# PLL1.net
KiCad netlist of a schematic drawn in Altium Designer
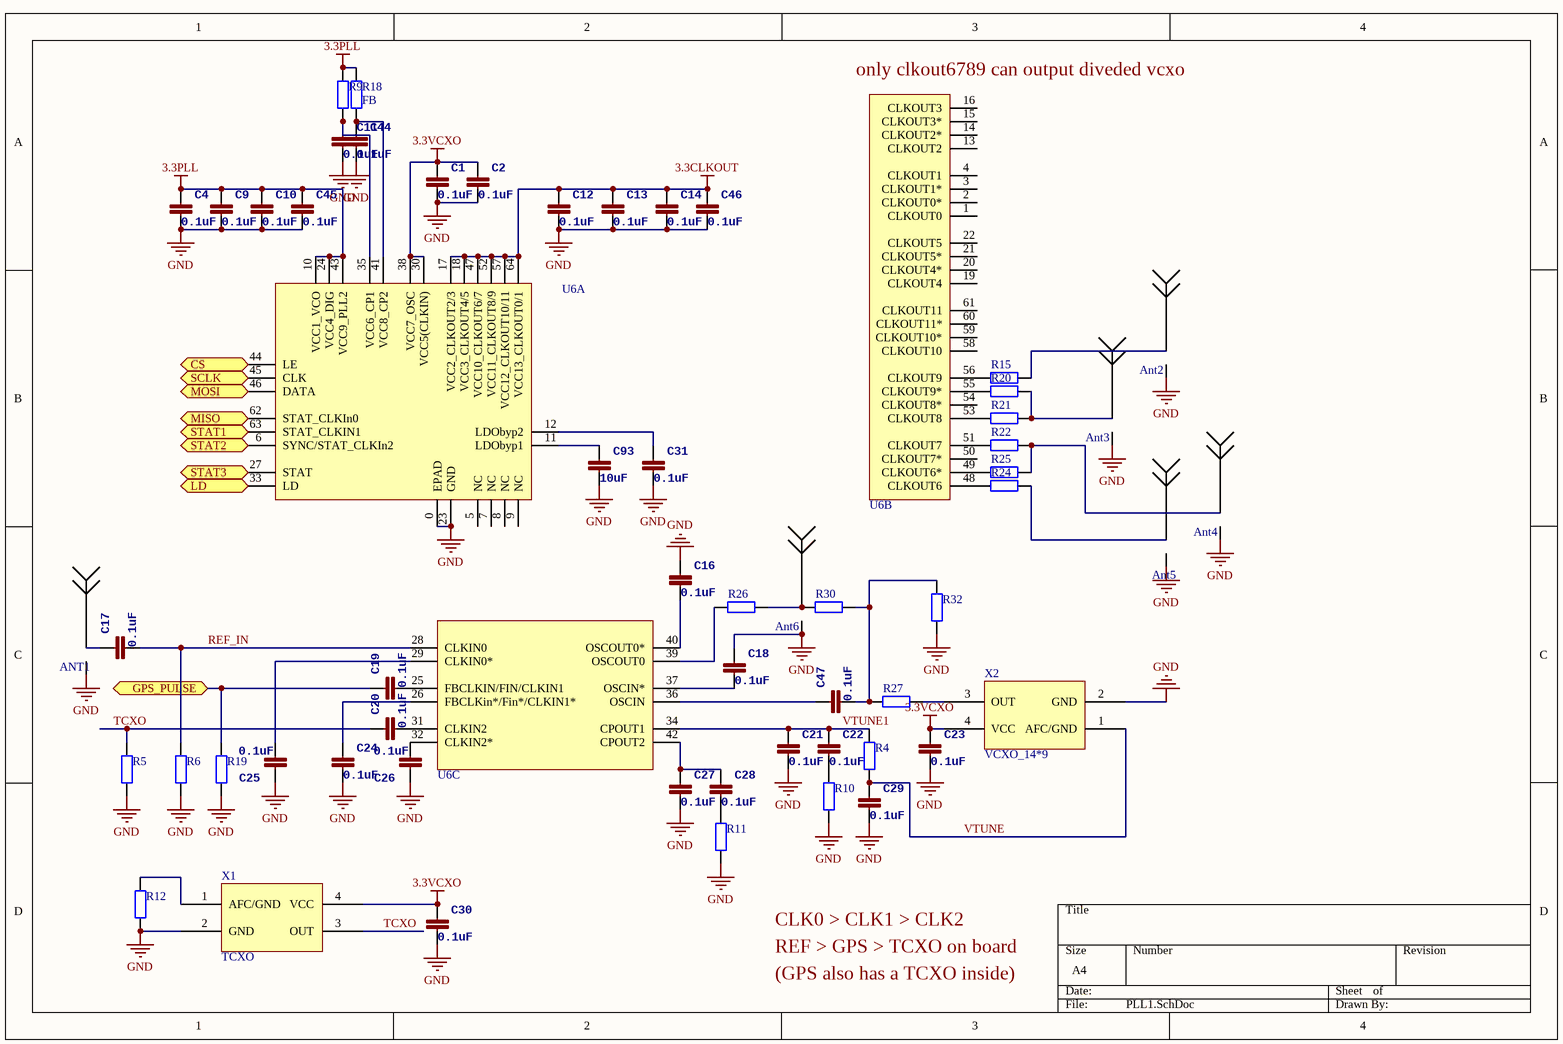
[diagram p0: PLL1.SchDoc]

(export (version "E")
  (design (tool "Eeschema 10.0.6"))
  (components
    (comp (ref "ANT1") (value "Antenna") (footprint "SMA-2B") (libsource (lib "F4SDR") (part "Antenna")))
    (comp (ref "Ant2") (value "Antenna") (footprint "SMA-2B") (libsource (lib "F4SDR") (part "Antenna")))
    (comp (ref "Ant3") (value "Antenna") (footprint "SMA-2B") (libsource (lib "F4SDR") (part "Antenna")))
    (comp (ref "Ant4") (value "Antenna") (footprint "SMA-2B") (libsource (lib "F4SDR") (part "Antenna")))
    (comp (ref "Ant5") (value "Antenna") (footprint "SMA-2B") (libsource (lib "F4SDR") (part "Antenna")))
    (comp (ref "Ant6") (value "Antenna") (footprint "SMA-2B") (libsource (lib "F4SDR") (part "Antenna")))
    (comp (ref "C1")
      (value "0.1uF")
      (footprint "0402")
      (description "<b>Capacitor</b>\nStandard 0603 ceramic capacitor, and 0.1\" leaded capacitor.")
      (fields (field (name "PARTNO") "CC0402ZRY5V7BB104"))
      (libsource (lib "pixhawk2") (part "CAP0402-CAP"))
    )
    (comp (ref "C2")
      (value "0.1uF")
      (footprint "0402")
      (description "<b>Capacitor</b>\nStandard 0603 ceramic capacitor, and 0.1\" leaded capacitor.")
      (fields (field (name "PARTNO") "CC0402ZRY5V7BB104"))
      (libsource (lib "pixhawk2") (part "CAP0402-CAP"))
    )
    (comp (ref "C4")
      (value "0.1uF")
      (footprint "0402")
      (description "<b>Capacitor</b>\nStandard 0603 ceramic capacitor, and 0.1\" leaded capacitor.")
      (fields (field (name "PARTNO") "CC0402ZRY5V7BB104"))
      (libsource (lib "pixhawk2") (part "CAP0402-CAP"))
    )
    (comp (ref "C9")
      (value "0.1uF")
      (footprint "0402")
      (description "<b>Capacitor</b>\nStandard 0603 ceramic capacitor, and 0.1\" leaded capacitor.")
      (fields (field (name "PARTNO") "CC0402ZRY5V7BB104"))
      (libsource (lib "pixhawk2") (part "CAP0402-CAP"))
    )
    (comp (ref "C10")
      (value "0.1uF")
      (footprint "0402")
      (description "<b>Capacitor</b>\nStandard 0603 ceramic capacitor, and 0.1\" leaded capacitor.")
      (fields (field (name "PARTNO") "CC0402ZRY5V7BB104"))
      (libsource (lib "pixhawk2") (part "CAP0402-CAP"))
    )
    (comp (ref "C11")
      (value "0.1uF")
      (footprint "0402")
      (description "<b>Capacitor</b>\nStandard 0603 ceramic capacitor, and 0.1\" leaded capacitor.")
      (fields (field (name "PARTNO") "CC0402ZRY5V7BB104"))
      (libsource (lib "pixhawk2") (part "CAP0402-CAP"))
    )
    (comp (ref "C12")
      (value "0.1uF")
      (footprint "0402")
      (description "<b>Capacitor</b>\nStandard 0603 ceramic capacitor, and 0.1\" leaded capacitor.")
      (fields (field (name "PARTNO") "CC0402ZRY5V7BB104"))
      (libsource (lib "pixhawk2") (part "CAP0402-CAP"))
    )
    (comp (ref "C13")
      (value "0.1uF")
      (footprint "0402")
      (description "<b>Capacitor</b>\nStandard 0603 ceramic capacitor, and 0.1\" leaded capacitor.")
      (fields (field (name "PARTNO") "CC0402ZRY5V7BB104"))
      (libsource (lib "pixhawk2") (part "CAP0402-CAP"))
    )
    (comp (ref "C14")
      (value "0.1uF")
      (footprint "0402")
      (description "<b>Capacitor</b>\nStandard 0603 ceramic capacitor, and 0.1\" leaded capacitor.")
      (fields (field (name "PARTNO") "CC0402ZRY5V7BB104"))
      (libsource (lib "pixhawk2") (part "CAP0402-CAP"))
    )
    (comp (ref "C16")
      (value "0.1uF")
      (footprint "0402")
      (description "<b>Capacitor</b>\nStandard 0603 ceramic capacitor, and 0.1\" leaded capacitor.")
      (fields (field (name "PARTNO") "CC0402ZRY5V7BB104"))
      (libsource (lib "pixhawk2") (part "CAP0402-CAP"))
    )
    (comp (ref "C17")
      (value "0.1uF")
      (footprint "0402")
      (description "<b>Capacitor</b>\nStandard 0603 ceramic capacitor, and 0.1\" leaded capacitor.")
      (fields (field (name "PARTNO") "CC0402ZRY5V7BB104"))
      (libsource (lib "") (part "CAP0402-CAP_1"))
    )
    (comp (ref "C18")
      (value "0.1uF")
      (footprint "0402")
      (description "<b>Capacitor</b>\nStandard 0603 ceramic capacitor, and 0.1\" leaded capacitor.")
      (fields (field (name "PARTNO") "CC0402ZRY5V7BB104"))
      (libsource (lib "pixhawk2") (part "CAP0402-CAP"))
    )
    (comp (ref "C19")
      (value "0.1uF")
      (footprint "0402")
      (description "<b>Capacitor</b>\nStandard 0603 ceramic capacitor, and 0.1\" leaded capacitor.")
      (fields (field (name "PARTNO") "CC0402ZRY5V7BB104"))
      (libsource (lib "") (part "CAP0402-CAP_1"))
    )
    (comp (ref "C20")
      (value "0.1uF")
      (footprint "0402")
      (description "<b>Capacitor</b>\nStandard 0603 ceramic capacitor, and 0.1\" leaded capacitor.")
      (fields (field (name "PARTNO") "CC0402ZRY5V7BB104"))
      (libsource (lib "") (part "CAP0402-CAP_1"))
    )
    (comp (ref "C21")
      (value "0.1uF")
      (footprint "0402")
      (description "<b>Capacitor</b>\nStandard 0603 ceramic capacitor, and 0.1\" leaded capacitor.")
      (fields (field (name "PARTNO") "CC0402ZRY5V7BB104"))
      (libsource (lib "pixhawk2") (part "CAP0402-CAP"))
    )
    (comp (ref "C22")
      (value "0.1uF")
      (footprint "0402")
      (description "<b>Capacitor</b>\nStandard 0603 ceramic capacitor, and 0.1\" leaded capacitor.")
      (fields (field (name "PARTNO") "CC0402ZRY5V7BB104"))
      (libsource (lib "pixhawk2") (part "CAP0402-CAP"))
    )
    (comp (ref "C23")
      (value "0.1uF")
      (footprint "0402")
      (description "<b>Capacitor</b>\nStandard 0603 ceramic capacitor, and 0.1\" leaded capacitor.")
      (fields (field (name "PARTNO") "CC0402ZRY5V7BB104"))
      (libsource (lib "pixhawk2") (part "CAP0402-CAP"))
    )
    (comp (ref "C24")
      (value "0.1uF")
      (footprint "0402")
      (description "<b>Capacitor</b>\nStandard 0603 ceramic capacitor, and 0.1\" leaded capacitor.")
      (fields (field (name "PARTNO") "CC0402ZRY5V7BB104"))
      (libsource (lib "pixhawk2") (part "CAP0402-CAP"))
    )
    (comp (ref "C25")
      (value "0.1uF")
      (footprint "0402")
      (description "<b>Capacitor</b>\nStandard 0603 ceramic capacitor, and 0.1\" leaded capacitor.")
      (fields (field (name "PARTNO") "CC0402ZRY5V7BB104"))
      (libsource (lib "") (part "CAP0402-CAP_2"))
    )
    (comp (ref "C26")
      (value "0.1uF")
      (footprint "0402")
      (description "<b>Capacitor</b>\nStandard 0603 ceramic capacitor, and 0.1\" leaded capacitor.")
      (fields (field (name "PARTNO") "CC0402ZRY5V7BB104"))
      (libsource (lib "") (part "CAP0402-CAP_2"))
    )
    (comp (ref "C27")
      (value "0.1uF")
      (footprint "0402")
      (description "<b>Capacitor</b>\nStandard 0603 ceramic capacitor, and 0.1\" leaded capacitor.")
      (fields (field (name "PARTNO") "CC0402ZRY5V7BB104"))
      (libsource (lib "pixhawk2") (part "CAP0402-CAP"))
    )
    (comp (ref "C28")
      (value "0.1uF")
      (footprint "0402")
      (description "<b>Capacitor</b>\nStandard 0603 ceramic capacitor, and 0.1\" leaded capacitor.")
      (fields (field (name "PARTNO") "CC0402ZRY5V7BB104"))
      (libsource (lib "pixhawk2") (part "CAP0402-CAP"))
    )
    (comp (ref "C29")
      (value "0.1uF")
      (footprint "0402")
      (description "<b>Capacitor</b>\nStandard 0603 ceramic capacitor, and 0.1\" leaded capacitor.")
      (fields (field (name "PARTNO") "CC0402ZRY5V7BB104"))
      (libsource (lib "pixhawk2") (part "CAP0402-CAP"))
    )
    (comp (ref "C30")
      (value "0.1uF")
      (footprint "0402")
      (description "<b>Capacitor</b>\nStandard 0603 ceramic capacitor, and 0.1\" leaded capacitor.")
      (fields (field (name "PARTNO") "CC0402ZRY5V7BB104"))
      (libsource (lib "pixhawk2") (part "CAP0402-CAP"))
    )
    (comp (ref "C31")
      (value "0.1uF")
      (footprint "0402")
      (description "<b>Capacitor</b>\nStandard 0603 ceramic capacitor, and 0.1\" leaded capacitor.")
      (fields (field (name "PARTNO") "CC0402ZRY5V7BB104"))
      (libsource (lib "pixhawk2") (part "CAP0402-CAP"))
    )
    (comp (ref "C44")
      (value "0.1uF")
      (footprint "0402")
      (description "<b>Capacitor</b>\nStandard 0603 ceramic capacitor, and 0.1\" leaded capacitor.")
      (fields (field (name "PARTNO") "CC0402ZRY5V7BB104"))
      (libsource (lib "pixhawk2") (part "CAP0402-CAP"))
    )
    (comp (ref "C45")
      (value "0.1uF")
      (footprint "0402")
      (description "<b>Capacitor</b>\nStandard 0603 ceramic capacitor, and 0.1\" leaded capacitor.")
      (fields (field (name "PARTNO") "CC0402ZRY5V7BB104"))
      (libsource (lib "pixhawk2") (part "CAP0402-CAP"))
    )
    (comp (ref "C46")
      (value "0.1uF")
      (footprint "0402")
      (description "<b>Capacitor</b>\nStandard 0603 ceramic capacitor, and 0.1\" leaded capacitor.")
      (fields (field (name "PARTNO") "CC0402ZRY5V7BB104"))
      (libsource (lib "pixhawk2") (part "CAP0402-CAP"))
    )
    (comp (ref "C47")
      (value "0.1uF")
      (footprint "0402")
      (description "<b>Capacitor</b>\nStandard 0603 ceramic capacitor, and 0.1\" leaded capacitor.")
      (fields (field (name "PARTNO") "CC0402ZRY5V7BB104"))
      (libsource (lib "") (part "CAP0402-CAP_1"))
    )
    (comp (ref "C93")
      (value "10uF")
      (footprint "0603L")
      (description "<b>Capacitor</b>\nStandard 0603 ceramic capacitor, and 0.1\" leaded capacitor.")
      (fields (field (name "PARTNO") "CC0402ZRY5V7BB104"))
      (libsource (lib "pixhawk2") (part "CAP0402-CAP"))
    )
    (comp (ref "R4")
      (value "~")
      (footprint "0402")
      (description "Resistor")
      (fields (field (name "PUBLISHER") "Altium Limited"))
      (libsource (lib "") (part "Res2_1"))
    )
    (comp (ref "R5")
      (value "~")
      (footprint "0402")
      (description "Resistor")
      (fields (field (name "PUBLISHER") "Altium Limited"))
      (libsource (lib "Miscellaneous Devices") (part "Res2"))
    )
    (comp (ref "R6")
      (value "~")
      (footprint "0402")
      (description "Resistor")
      (fields (field (name "PUBLISHER") "Altium Limited"))
      (libsource (lib "") (part "Res2_1"))
    )
    (comp (ref "R9")
      (value "~")
      (footprint "0402")
      (description "Resistor")
      (fields (field (name "PUBLISHER") "Altium Limited"))
      (libsource (lib "Miscellaneous Devices") (part "Res2"))
    )
    (comp (ref "R10")
      (value "~")
      (footprint "0402")
      (description "Resistor")
      (fields (field (name "PUBLISHER") "Altium Limited"))
      (libsource (lib "") (part "Res2_1"))
    )
    (comp (ref "R11")
      (value "~")
      (footprint "0402")
      (description "Resistor")
      (fields (field (name "PUBLISHER") "Altium Limited"))
      (libsource (lib "") (part "Res2_1"))
    )
    (comp (ref "R12")
      (value "~")
      (footprint "0402")
      (description "Resistor")
      (fields (field (name "PUBLISHER") "Altium Limited"))
      (libsource (lib "") (part "Res2_1"))
    )
    (comp (ref "R15")
      (value "~")
      (footprint "0402")
      (description "Resistor")
      (fields (field (name "PUBLISHER") "Altium Limited"))
      (libsource (lib "") (part "Res2_2"))
    )
    (comp (ref "R18")
      (value "FB")
      (footprint "0402")
      (description "Resistor")
      (fields (field (name "PUBLISHER") "Altium Limited"))
      (libsource (lib "Miscellaneous Devices") (part "Res2"))
    )
    (comp (ref "R19")
      (value "~")
      (footprint "0402")
      (description "Resistor")
      (fields (field (name "PUBLISHER") "Altium Limited"))
      (libsource (lib "Miscellaneous Devices") (part "Res2"))
    )
    (comp (ref "R20")
      (value "~")
      (footprint "0402")
      (description "Resistor")
      (fields (field (name "PUBLISHER") "Altium Limited"))
      (libsource (lib "") (part "Res2_2"))
    )
    (comp (ref "R21")
      (value "~")
      (footprint "0402")
      (description "Resistor")
      (fields (field (name "PUBLISHER") "Altium Limited"))
      (libsource (lib "") (part "Res2_2"))
    )
    (comp (ref "R22")
      (value "~")
      (footprint "0402")
      (description "Resistor")
      (fields (field (name "PUBLISHER") "Altium Limited"))
      (libsource (lib "") (part "Res2_2"))
    )
    (comp (ref "R24")
      (value "~")
      (footprint "0402")
      (description "Resistor")
      (fields (field (name "PUBLISHER") "Altium Limited"))
      (libsource (lib "") (part "Res2_2"))
    )
    (comp (ref "R25")
      (value "~")
      (footprint "0402")
      (description "Resistor")
      (fields (field (name "PUBLISHER") "Altium Limited"))
      (libsource (lib "") (part "Res2_2"))
    )
    (comp (ref "R26")
      (value "~")
      (footprint "0402")
      (description "Resistor")
      (fields (field (name "PUBLISHER") "Altium Limited"))
      (libsource (lib "") (part "Res2_2"))
    )
    (comp (ref "R27")
      (value "~")
      (footprint "0402")
      (description "Resistor")
      (fields (field (name "PUBLISHER") "Altium Limited"))
      (libsource (lib "") (part "Res2_2"))
    )
    (comp (ref "R30")
      (value "~")
      (footprint "0402")
      (description "Resistor")
      (fields (field (name "PUBLISHER") "Altium Limited"))
      (libsource (lib "") (part "Res2_2"))
    )
    (comp (ref "R32")
      (value "~")
      (footprint "0402")
      (description "Resistor")
      (fields (field (name "PUBLISHER") "Altium Limited"))
      (libsource (lib "") (part "Res2_1"))
    )
    (comp (ref "U6") (value "LMK04816") (footprint "LMK04816") (libsource (lib "F4SDR") (part "LMK04816")))
    (comp (ref "X1") (value "TCXO") (footprint "TXC_7Q") (libsource (lib "F4SDR") (part "OSC_40M")))
    (comp (ref "X2") (value "VCXO_14*9") (footprint "CRYSTEK-9*14") (libsource (lib "") (part "OSC_40M_1")))
  )
  (nets
    (net (code "1") (name "/CS") (class "Default")
      (node (ref "U6") (pin "44") (pinfunction "LE_44") (pintype "passive"))
    )
    (net (code "2") (name "/GPS_PULSE") (class "Default")
      (node (ref "C19") (pin "1") (pinfunction "1_1") (pintype "passive"))
      (node (ref "R19") (pin "2") (pinfunction "2_2") (pintype "passive"))
    )
    (net (code "3") (name "/LD") (class "Default")
      (node (ref "U6") (pin "33") (pinfunction "LD_33") (pintype "passive"))
    )
    (net (code "4") (name "/MISO") (class "Default")
      (node (ref "U6") (pin "62") (pinfunction "STAT_CLKIn0_62") (pintype "passive"))
    )
    (net (code "5") (name "/MOSI") (class "Default")
      (node (ref "U6") (pin "46") (pinfunction "DATA_46") (pintype "passive"))
    )
    (net (code "6") (name "/REF_IN") (class "Default")
      (node (ref "C17") (pin "2") (pinfunction "2_2") (pintype "passive"))
      (node (ref "R6") (pin "1") (pinfunction "1_1") (pintype "passive"))
      (node (ref "U6") (pin "28") (pinfunction "CLKIN0_28") (pintype "passive"))
    )
    (net (code "7") (name "/SCLK") (class "Default")
      (node (ref "U6") (pin "45") (pinfunction "CLK_45") (pintype "passive"))
    )
    (net (code "8") (name "/STAT1") (class "Default")
      (node (ref "U6") (pin "63") (pinfunction "STAT_CLKIN1_63") (pintype "passive"))
    )
    (net (code "9") (name "/STAT2") (class "Default")
      (node (ref "U6") (pin "6") (pinfunction "SYNC/STAT_CLKIn2_6") (pintype "passive"))
    )
    (net (code "10") (name "/STAT3") (class "Default")
      (node (ref "U6") (pin "27") (pinfunction "STAT_27") (pintype "passive"))
    )
    (net (code "11") (name "/TCXO") (class "Default")
      (node (ref "C20") (pin "1") (pinfunction "1_1") (pintype "passive"))
      (node (ref "R5") (pin "2") (pinfunction "2_2") (pintype "passive"))
      (node (ref "X1") (pin "3") (pinfunction "OUT_3") (pintype "passive"))
    )
    (net (code "12") (name "/VTUNE") (class "Default")
      (node (ref "C29") (pin "1") (pinfunction "1_1") (pintype "passive"))
      (node (ref "R4") (pin "2") (pinfunction "2_2") (pintype "passive"))
      (node (ref "X2") (pin "1") (pinfunction "AFC/GND_1") (pintype "passive"))
    )
    (net (code "13") (name "/VTUNE1") (class "Default")
      (node (ref "C21") (pin "1") (pinfunction "1_1") (pintype "passive"))
      (node (ref "C22") (pin "1") (pinfunction "1_1") (pintype "passive"))
      (node (ref "R4") (pin "1") (pinfunction "1_1") (pintype "passive"))
      (node (ref "U6") (pin "34") (pinfunction "CPOUT1_34") (pintype "passive"))
    )
    (net (code "14") (name "3.3CLKOUT") (class "Default")
      (node (ref "C12") (pin "1") (pinfunction "1_1") (pintype "passive"))
      (node (ref "C13") (pin "1") (pinfunction "1_1") (pintype "passive"))
      (node (ref "C14") (pin "1") (pinfunction "1_1") (pintype "passive"))
      (node (ref "C46") (pin "1") (pinfunction "1_1") (pintype "passive"))
      (node (ref "U6") (pin "17") (pinfunction "VCC2_CLKOUT2/3_17") (pintype "passive"))
      (node (ref "U6") (pin "18") (pinfunction "VCC3_CLKOUT4/5_18") (pintype "passive"))
      (node (ref "U6") (pin "47") (pinfunction "VCC10_CLKOUT6/7_47") (pintype "passive"))
      (node (ref "U6") (pin "52") (pinfunction "VCC11_CLKOUT8/9_52") (pintype "passive"))
      (node (ref "U6") (pin "57") (pinfunction "VCC12_CLKOUT10/11_57") (pintype "passive"))
      (node (ref "U6") (pin "64") (pinfunction "VCC13_CLKOUT0/1_64") (pintype "passive"))
    )
    (net (code "15") (name "3.3PLL") (class "Default")
      (node (ref "C10") (pin "1") (pinfunction "1_1") (pintype "passive"))
      (node (ref "C4") (pin "1") (pinfunction "1_1") (pintype "passive"))
      (node (ref "C45") (pin "1") (pinfunction "1_1") (pintype "passive"))
      (node (ref "C9") (pin "1") (pinfunction "1_1") (pintype "passive"))
      (node (ref "R18") (pin "2") (pinfunction "2_2") (pintype "passive"))
      (node (ref "R9") (pin "2") (pinfunction "2_2") (pintype "passive"))
      (node (ref "U6") (pin "10") (pinfunction "VCC1_VCO_10") (pintype "passive"))
      (node (ref "U6") (pin "24") (pinfunction "VCC4_DIG_24") (pintype "passive"))
      (node (ref "U6") (pin "43") (pinfunction "VCC9_PLL2_43") (pintype "passive"))
    )
    (net (code "16") (name "3.3VCXO") (class "Default")
      (node (ref "C1") (pin "1") (pinfunction "1_1") (pintype "passive"))
      (node (ref "C2") (pin "1") (pinfunction "1_1") (pintype "passive"))
      (node (ref "C23") (pin "1") (pinfunction "1_1") (pintype "passive"))
      (node (ref "C30") (pin "1") (pinfunction "1_1") (pintype "passive"))
      (node (ref "U6") (pin "30") (pinfunction "VCC5(CLKIN)_30") (pintype "passive"))
      (node (ref "U6") (pin "38") (pinfunction "VCC7_OSC_38") (pintype "passive"))
      (node (ref "X1") (pin "4") (pinfunction "VCC_4") (pintype "passive"))
      (node (ref "X2") (pin "4") (pinfunction "VCC_4") (pintype "passive"))
    )
    (net (code "17") (name "GND") (class "Default")
      (node (ref "ANT1") (pin "GND") (pinfunction "G_GND") (pintype "passive"))
      (node (ref "Ant2") (pin "GND") (pinfunction "G_GND") (pintype "passive"))
      (node (ref "Ant3") (pin "GND") (pinfunction "G_GND") (pintype "passive"))
      (node (ref "Ant4") (pin "GND") (pinfunction "G_GND") (pintype "passive"))
      (node (ref "Ant5") (pin "GND") (pinfunction "G_GND") (pintype "passive"))
      (node (ref "Ant6") (pin "GND") (pinfunction "G_GND") (pintype "passive"))
      (node (ref "C1") (pin "2") (pinfunction "2_2") (pintype "passive"))
      (node (ref "C10") (pin "2") (pinfunction "2_2") (pintype "passive"))
      (node (ref "C11") (pin "2") (pinfunction "2_2") (pintype "passive"))
      (node (ref "C12") (pin "2") (pinfunction "2_2") (pintype "passive"))
      (node (ref "C13") (pin "2") (pinfunction "2_2") (pintype "passive"))
      (node (ref "C14") (pin "2") (pinfunction "2_2") (pintype "passive"))
      (node (ref "C16") (pin "1") (pinfunction "1_1") (pintype "passive"))
      (node (ref "C18") (pin "1") (pinfunction "1_1") (pintype "passive"))
      (node (ref "C2") (pin "2") (pinfunction "2_2") (pintype "passive"))
      (node (ref "C21") (pin "2") (pinfunction "2_2") (pintype "passive"))
      (node (ref "C23") (pin "2") (pinfunction "2_2") (pintype "passive"))
      (node (ref "C24") (pin "2") (pinfunction "2_2") (pintype "passive"))
      (node (ref "C25") (pin "1") (pinfunction "1_1") (pintype "passive"))
      (node (ref "C26") (pin "1") (pinfunction "1_1") (pintype "passive"))
      (node (ref "C27") (pin "2") (pinfunction "2_2") (pintype "passive"))
      (node (ref "C29") (pin "2") (pinfunction "2_2") (pintype "passive"))
      (node (ref "C30") (pin "2") (pinfunction "2_2") (pintype "passive"))
      (node (ref "C31") (pin "2") (pinfunction "2_2") (pintype "passive"))
      (node (ref "C4") (pin "2") (pinfunction "2_2") (pintype "passive"))
      (node (ref "C44") (pin "2") (pinfunction "2_2") (pintype "passive"))
      (node (ref "C45") (pin "2") (pinfunction "2_2") (pintype "passive"))
      (node (ref "C46") (pin "2") (pinfunction "2_2") (pintype "passive"))
      (node (ref "C9") (pin "2") (pinfunction "2_2") (pintype "passive"))
      (node (ref "C93") (pin "2") (pinfunction "2_2") (pintype "passive"))
      (node (ref "R10") (pin "2") (pinfunction "2_2") (pintype "passive"))
      (node (ref "R11") (pin "2") (pinfunction "2_2") (pintype "passive"))
      (node (ref "R12") (pin "2") (pinfunction "2_2") (pintype "passive"))
      (node (ref "R19") (pin "1") (pinfunction "1_1") (pintype "passive"))
      (node (ref "R32") (pin "2") (pinfunction "2_2") (pintype "passive"))
      (node (ref "R5") (pin "1") (pinfunction "1_1") (pintype "passive"))
      (node (ref "R6") (pin "2") (pinfunction "2_2") (pintype "passive"))
      (node (ref "U6") (pin "0") (pinfunction "EPAD_0") (pintype "passive"))
      (node (ref "U6") (pin "23") (pinfunction "GND_23") (pintype "passive"))
      (node (ref "X1") (pin "2") (pinfunction "GND_2") (pintype "passive"))
      (node (ref "X2") (pin "2") (pinfunction "GND_2") (pintype "passive"))
    )
    (net (code "18") (name "Net-(ANT1-Pad1)") (class "Default")
      (node (ref "ANT1") (pin "1") (pinfunction "1_1") (pintype "passive"))
      (node (ref "C17") (pin "1") (pinfunction "1_1") (pintype "passive"))
    )
    (net (code "19") (name "Net-(Ant2-Pad1)") (class "Default")
      (node (ref "Ant2") (pin "1") (pinfunction "1_1") (pintype "passive"))
      (node (ref "R15") (pin "2") (pinfunction "2_2") (pintype "passive"))
    )
    (net (code "20") (name "Net-(Ant3-Pad1)") (class "Default")
      (node (ref "Ant3") (pin "1") (pinfunction "1_1") (pintype "passive"))
      (node (ref "R20") (pin "2") (pinfunction "2_2") (pintype "passive"))
      (node (ref "R21") (pin "2") (pinfunction "2_2") (pintype "passive"))
    )
    (net (code "21") (name "Net-(Ant4-Pad1)") (class "Default")
      (node (ref "Ant4") (pin "1") (pinfunction "1_1") (pintype "passive"))
      (node (ref "R22") (pin "2") (pinfunction "2_2") (pintype "passive"))
      (node (ref "R25") (pin "2") (pinfunction "2_2") (pintype "passive"))
    )
    (net (code "22") (name "Net-(Ant5-Pad1)") (class "Default")
      (node (ref "Ant5") (pin "1") (pinfunction "1_1") (pintype "passive"))
      (node (ref "R24") (pin "2") (pinfunction "2_2") (pintype "passive"))
    )
    (net (code "23") (name "Net-(Ant6-Pad1)") (class "Default")
      (node (ref "Ant6") (pin "1") (pinfunction "1_1") (pintype "passive"))
      (node (ref "R26") (pin "2") (pinfunction "2_2") (pintype "passive"))
      (node (ref "R30") (pin "1") (pinfunction "1_1") (pintype "passive"))
    )
    (net (code "24") (name "Net-(C22-Pad2)") (class "Default")
      (node (ref "C22") (pin "2") (pinfunction "2_2") (pintype "passive"))
      (node (ref "R10") (pin "1") (pinfunction "1_1") (pintype "passive"))
    )
    (net (code "25") (name "Net-(C28-Pad2)") (class "Default")
      (node (ref "C28") (pin "2") (pinfunction "2_2") (pintype "passive"))
      (node (ref "R11") (pin "1") (pinfunction "1_1") (pintype "passive"))
    )
    (net (code "26") (name "Net-(C47-Pad2)") (class "Default")
      (node (ref "C47") (pin "2") (pinfunction "2_2") (pintype "passive"))
      (node (ref "R27") (pin "1") (pinfunction "1_1") (pintype "passive"))
      (node (ref "R30") (pin "2") (pinfunction "2_2") (pintype "passive"))
      (node (ref "R32") (pin "1") (pinfunction "1_1") (pintype "passive"))
    )
    (net (code "27") (name "Net-(U6A-LDObyp1)") (class "Default")
      (node (ref "C93") (pin "1") (pinfunction "1_1") (pintype "passive"))
      (node (ref "U6") (pin "11") (pinfunction "LDObyp1_11") (pintype "passive"))
    )
    (net (code "28") (name "Net-(U6A-LDObyp2)") (class "Default")
      (node (ref "C31") (pin "1") (pinfunction "1_1") (pintype "passive"))
      (node (ref "U6") (pin "12") (pinfunction "LDObyp2_12") (pintype "passive"))
    )
    (net (code "29") (name "Net-(U6A-VCC6_CP1)") (class "Default")
      (node (ref "C11") (pin "1") (pinfunction "1_1") (pintype "passive"))
      (node (ref "R9") (pin "1") (pinfunction "1_1") (pintype "passive"))
      (node (ref "U6") (pin "35") (pinfunction "VCC6_CP1_35") (pintype "passive"))
    )
    (net (code "30") (name "Net-(U6A-VCC8_CP2)") (class "Default")
      (node (ref "C44") (pin "1") (pinfunction "1_1") (pintype "passive"))
      (node (ref "R18") (pin "1") (pinfunction "1_1") (pintype "passive"))
      (node (ref "U6") (pin "41") (pinfunction "VCC8_CP2_41") (pintype "passive"))
    )
    (net (code "31") (name "Net-(U6B-CLKOUT6)") (class "Default")
      (node (ref "R24") (pin "1") (pinfunction "1_1") (pintype "passive"))
      (node (ref "U6") (pin "48") (pinfunction "CLKOUT6_48") (pintype "passive"))
    )
    (net (code "32") (name "Net-(U6B-CLKOUT6*)") (class "Default")
      (node (ref "R25") (pin "1") (pinfunction "1_1") (pintype "passive"))
      (node (ref "U6") (pin "49") (pinfunction "CLKOUT6*_49") (pintype "passive"))
    )
    (net (code "33") (name "Net-(U6B-CLKOUT7)") (class "Default")
      (node (ref "R22") (pin "1") (pinfunction "1_1") (pintype "passive"))
      (node (ref "U6") (pin "51") (pinfunction "CLKOUT7_51") (pintype "passive"))
    )
    (net (code "34") (name "Net-(U6B-CLKOUT8)") (class "Default")
      (node (ref "R21") (pin "1") (pinfunction "1_1") (pintype "passive"))
      (node (ref "U6") (pin "53") (pinfunction "CLKOUT8_53") (pintype "passive"))
    )
    (net (code "35") (name "Net-(U6B-CLKOUT9)") (class "Default")
      (node (ref "R15") (pin "1") (pinfunction "1_1") (pintype "passive"))
      (node (ref "U6") (pin "56") (pinfunction "CLKOUT9_56") (pintype "passive"))
    )
    (net (code "36") (name "Net-(U6B-CLKOUT9*)") (class "Default")
      (node (ref "R20") (pin "1") (pinfunction "1_1") (pintype "passive"))
      (node (ref "U6") (pin "55") (pinfunction "CLKOUT9*_55") (pintype "passive"))
    )
    (net (code "37") (name "Net-(U6C-CLKIN0*)") (class "Default")
      (node (ref "C25") (pin "2") (pinfunction "2_2") (pintype "passive"))
      (node (ref "U6") (pin "29") (pinfunction "CLKIN0*_29") (pintype "passive"))
    )
    (net (code "38") (name "Net-(U6C-CLKIN2)") (class "Default")
      (node (ref "C20") (pin "2") (pinfunction "2_2") (pintype "passive"))
      (node (ref "U6") (pin "31") (pinfunction "CLKIN2_31") (pintype "passive"))
    )
    (net (code "39") (name "Net-(U6C-CLKIN2*)") (class "Default")
      (node (ref "C26") (pin "2") (pinfunction "2_2") (pintype "passive"))
      (node (ref "U6") (pin "32") (pinfunction "CLKIN2*_32") (pintype "passive"))
    )
    (net (code "40") (name "Net-(U6C-CPOUT2)") (class "Default")
      (node (ref "C27") (pin "1") (pinfunction "1_1") (pintype "passive"))
      (node (ref "C28") (pin "1") (pinfunction "1_1") (pintype "passive"))
      (node (ref "U6") (pin "42") (pinfunction "CPOUT2_42") (pintype "passive"))
    )
    (net (code "41") (name "Net-(U6C-FBCLKIN{slash}FIN{slash}CLKIN1)") (class "Default")
      (node (ref "C19") (pin "2") (pinfunction "2_2") (pintype "passive"))
      (node (ref "U6") (pin "25") (pinfunction "FBCLKIN/FIN/CLKIN1_25") (pintype "passive"))
    )
    (net (code "42") (name "Net-(U6C-FBCLKin*{slash}Fin*{slash}CLKIN1*)") (class "Default")
      (node (ref "C24") (pin "1") (pinfunction "1_1") (pintype "passive"))
      (node (ref "U6") (pin "26") (pinfunction "FBCLKin*/Fin*/CLKIN1*_26") (pintype "passive"))
    )
    (net (code "43") (name "Net-(U6C-OSCIN)") (class "Default")
      (node (ref "C47") (pin "1") (pinfunction "1_1") (pintype "passive"))
      (node (ref "U6") (pin "36") (pinfunction "OSCIN_36") (pintype "passive"))
    )
    (net (code "44") (name "Net-(U6C-OSCIN*)") (class "Default")
      (node (ref "C18") (pin "2") (pinfunction "2_2") (pintype "passive"))
      (node (ref "U6") (pin "37") (pinfunction "OSCIN*_37") (pintype "passive"))
    )
    (net (code "45") (name "Net-(U6C-OSCOUT0)") (class "Default")
      (node (ref "R26") (pin "1") (pinfunction "1_1") (pintype "passive"))
      (node (ref "U6") (pin "39") (pinfunction "OSCOUT0_39") (pintype "passive"))
    )
    (net (code "46") (name "Net-(U6C-OSCOUT0*)") (class "Default")
      (node (ref "C16") (pin "2") (pinfunction "2_2") (pintype "passive"))
      (node (ref "U6") (pin "40") (pinfunction "OSCOUT0*_40") (pintype "passive"))
    )
    (net (code "47") (name "Net-(X1-AFC{slash}GND)") (class "Default")
      (node (ref "R12") (pin "1") (pinfunction "1_1") (pintype "passive"))
      (node (ref "X1") (pin "1") (pinfunction "AFC/GND_1") (pintype "passive"))
    )
    (net (code "48") (name "Net-(X2-OUT)") (class "Default")
      (node (ref "R27") (pin "2") (pinfunction "2_2") (pintype "passive"))
      (node (ref "X2") (pin "3") (pinfunction "OUT_3") (pintype "passive"))
    )
    (net (code "49") (name "unconnected-(U6A-NC-Pad5)") (class "Default")
      (node (ref "U6") (pin "5") (pinfunction "NC_5") (pintype "passive"))
    )
    (net (code "50") (name "unconnected-(U6A-NC-Pad7)") (class "Default")
      (node (ref "U6") (pin "7") (pinfunction "NC_7") (pintype "passive"))
    )
    (net (code "51") (name "unconnected-(U6A-NC-Pad8)") (class "Default")
      (node (ref "U6") (pin "8") (pinfunction "NC_8") (pintype "passive"))
    )
    (net (code "52") (name "unconnected-(U6A-NC-Pad9)") (class "Default")
      (node (ref "U6") (pin "9") (pinfunction "NC_9") (pintype "passive"))
    )
    (net (code "53") (name "unconnected-(U6B-CLKOUT0*-Pad2)") (class "Default")
      (node (ref "U6") (pin "2") (pinfunction "CLKOUT0*_2") (pintype "passive"))
    )
    (net (code "54") (name "unconnected-(U6B-CLKOUT0-Pad1)") (class "Default")
      (node (ref "U6") (pin "1") (pinfunction "CLKOUT0_1") (pintype "passive"))
    )
    (net (code "55") (name "unconnected-(U6B-CLKOUT1*-Pad3)") (class "Default")
      (node (ref "U6") (pin "3") (pinfunction "CLKOUT1*_3") (pintype "passive"))
    )
    (net (code "56") (name "unconnected-(U6B-CLKOUT1-Pad4)") (class "Default")
      (node (ref "U6") (pin "4") (pinfunction "CLKOUT1_4") (pintype "passive"))
    )
    (net (code "57") (name "unconnected-(U6B-CLKOUT2*-Pad14)") (class "Default")
      (node (ref "U6") (pin "14") (pinfunction "CLKOUT2*_14") (pintype "passive"))
    )
    (net (code "58") (name "unconnected-(U6B-CLKOUT2-Pad13)") (class "Default")
      (node (ref "U6") (pin "13") (pinfunction "CLKOUT2_13") (pintype "passive"))
    )
    (net (code "59") (name "unconnected-(U6B-CLKOUT3*-Pad15)") (class "Default")
      (node (ref "U6") (pin "15") (pinfunction "CLKOUT3*_15") (pintype "passive"))
    )
    (net (code "60") (name "unconnected-(U6B-CLKOUT3-Pad16)") (class "Default")
      (node (ref "U6") (pin "16") (pinfunction "CLKOUT3_16") (pintype "passive"))
    )
    (net (code "61") (name "unconnected-(U6B-CLKOUT4*-Pad20)") (class "Default")
      (node (ref "U6") (pin "20") (pinfunction "CLKOUT4*_20") (pintype "passive"))
    )
    (net (code "62") (name "unconnected-(U6B-CLKOUT4-Pad19)") (class "Default")
      (node (ref "U6") (pin "19") (pinfunction "CLKOUT4_19") (pintype "passive"))
    )
    (net (code "63") (name "unconnected-(U6B-CLKOUT5*-Pad21)") (class "Default")
      (node (ref "U6") (pin "21") (pinfunction "CLKOUT5*_21") (pintype "passive"))
    )
    (net (code "64") (name "unconnected-(U6B-CLKOUT5-Pad22)") (class "Default")
      (node (ref "U6") (pin "22") (pinfunction "CLKOUT5_22") (pintype "passive"))
    )
    (net (code "65") (name "unconnected-(U6B-CLKOUT7*-Pad50)") (class "Default")
      (node (ref "U6") (pin "50") (pinfunction "CLKOUT7*_50") (pintype "passive"))
    )
    (net (code "66") (name "unconnected-(U6B-CLKOUT8*-Pad54)") (class "Default")
      (node (ref "U6") (pin "54") (pinfunction "CLKOUT8*_54") (pintype "passive"))
    )
    (net (code "67") (name "unconnected-(U6B-CLKOUT10*-Pad59)") (class "Default")
      (node (ref "U6") (pin "59") (pinfunction "CLKOUT10*_59") (pintype "passive"))
    )
    (net (code "68") (name "unconnected-(U6B-CLKOUT10-Pad58)") (class "Default")
      (node (ref "U6") (pin "58") (pinfunction "CLKOUT10_58") (pintype "passive"))
    )
    (net (code "69") (name "unconnected-(U6B-CLKOUT11*-Pad60)") (class "Default")
      (node (ref "U6") (pin "60") (pinfunction "CLKOUT11*_60") (pintype "passive"))
    )
    (net (code "70") (name "unconnected-(U6B-CLKOUT11-Pad61)") (class "Default")
      (node (ref "U6") (pin "61") (pinfunction "CLKOUT11_61") (pintype "passive"))
    )
  )
)
